# LC709203F_breakout.net
KiCad netlist of a schematic drawn in EAGLE
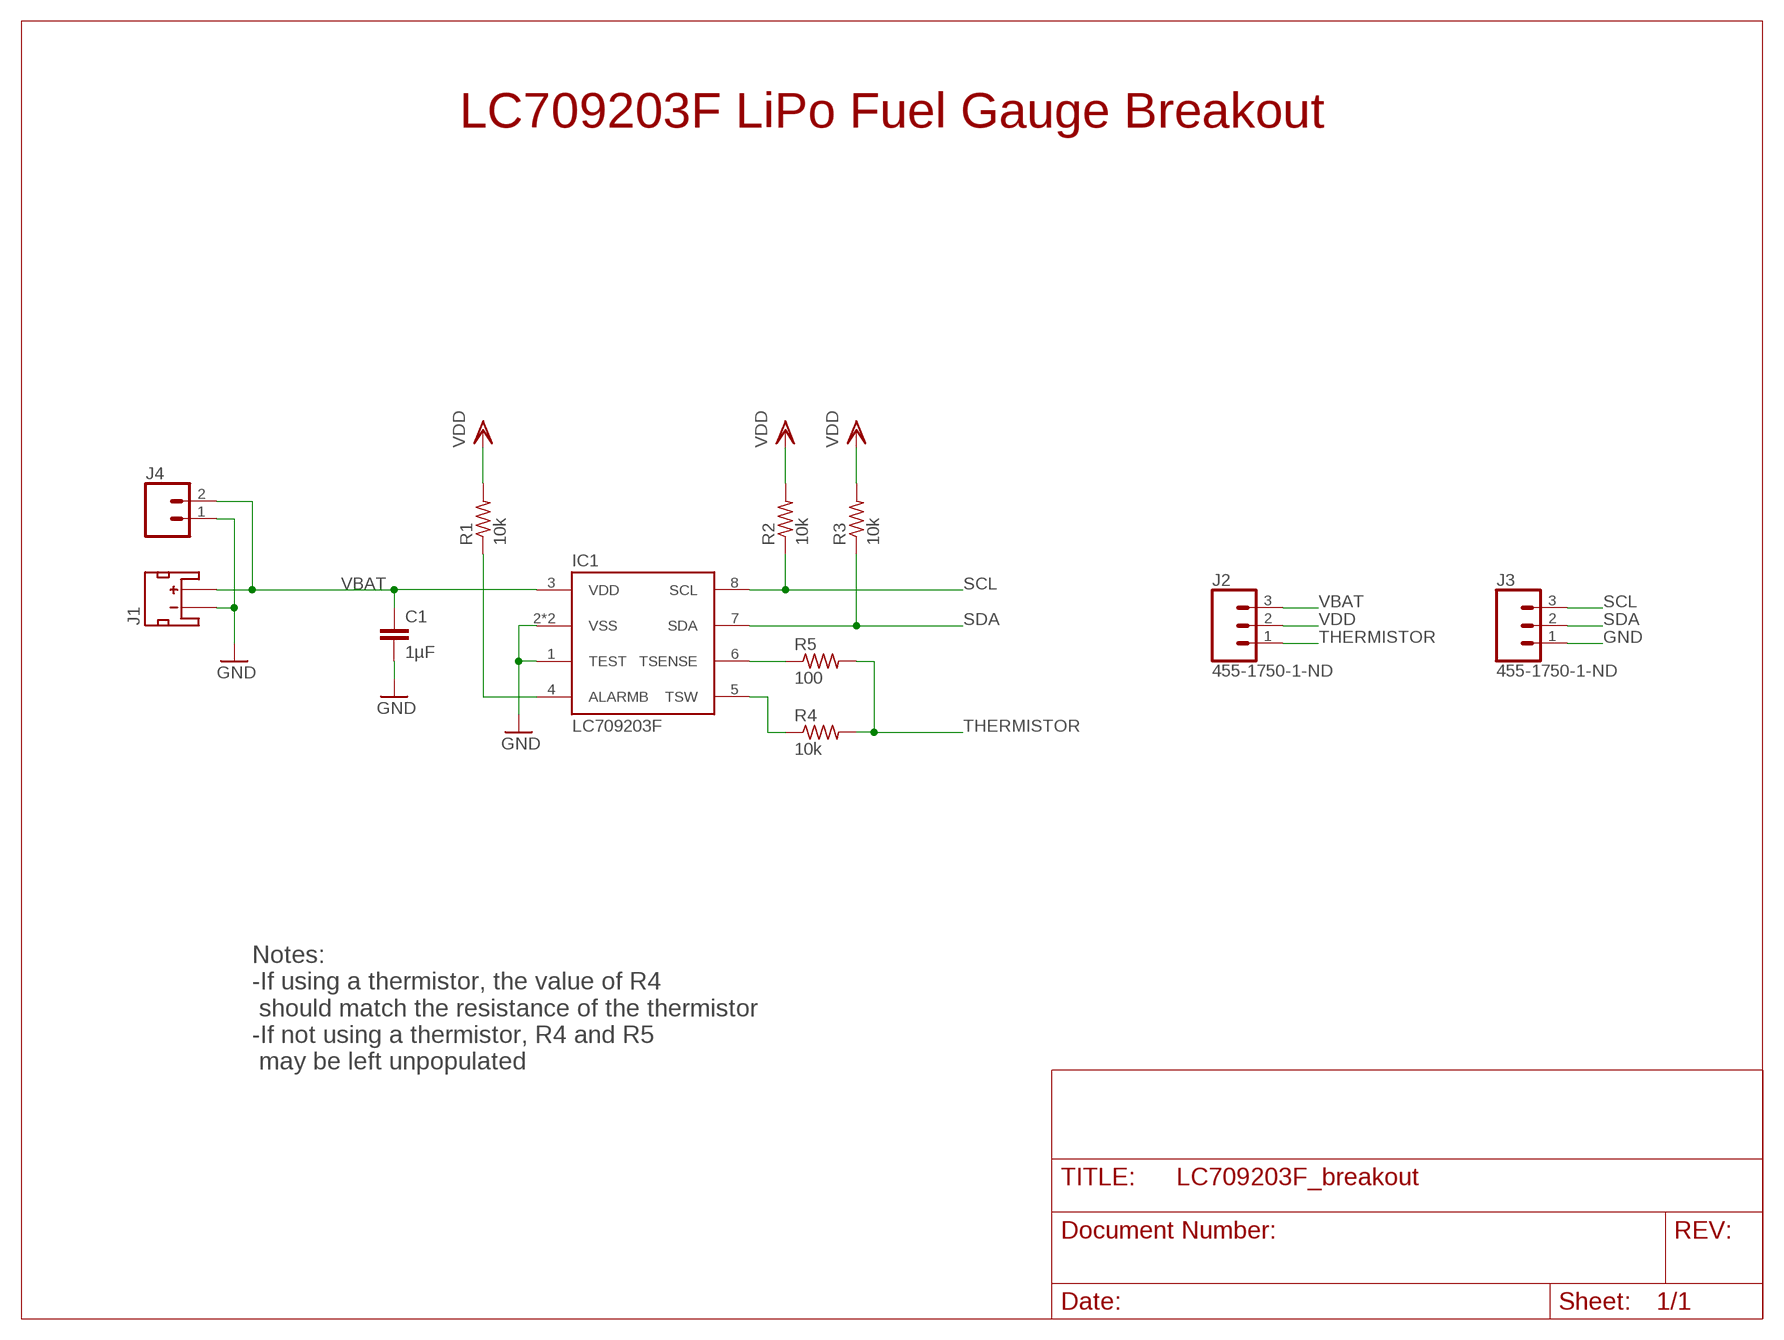
[diagram p0: schematic, sheet 1]

(export (version "E")
  (design (tool "Eeschema 10.0.6"))
  (components
    (comp (ref "C1")
      (value "1µF")
      (footprint "eagle-import:C0805")
      (fields
        (field (name "MANUFACTURER") "Murata Electronics North America")
        (field (name "PART#") "GRM21BR71A105KA01L")
        (field (name "TOLERANCE") "±10%")
      )
      (libsource (lib "eagle-import") (part "CAP_0805_MURATA_GRM_1UF"))
    )
    (comp (ref "IC1")
      (value "LC709203F")
      (footprint "eagle-import:WDFN8_ONSEMI")
      (fields (field (name "MANUFACTURER") "ON Semiconductor") (field (name "PART#") "LC709203FQH-01TWG"))
      (libsource (lib "eagle-import") (part "LC709203F"))
    )
    (comp (ref "J1")
      (value "S2B-PH-SM4-TB")
      (footprint "eagle-import:JST-2-SMD")
      (fields
        (field (name "MANUFACTURER") "JST Sales America Inc.")
        (field (name "PART#") "S2B-PH-SM4-TB(LF)(SN)")
      )
      (libsource (lib "eagle-import") (part "JST_2MM_MALE"))
    )
    (comp (ref "J2")
      (value "455-1750-1-ND")
      (footprint "eagle-import:1X03")
      (libsource (lib "eagle-import") (part "CONN_03"))
    )
    (comp (ref "J3")
      (value "455-1750-1-ND")
      (footprint "eagle-import:1X03")
      (libsource (lib "eagle-import") (part "CONN_03"))
    )
    (comp (ref "J4")
      (value "CONN_02")
      (footprint "eagle-import:1X02")
      (libsource (lib "eagle-import") (part "CONN_02"))
    )
    (comp (ref "R1")
      (value "10k")
      (footprint "eagle-import:R0805")
      (fields
        (field (name "MANUFACTURER") "Yageo")
        (field (name "PART#") "RC0805FR-0710KL")
        (field (name "POWER") "1/8W")
      )
      (libsource (lib "eagle-import") (part "RESISTOR_0805_YAGEO_RC_10K"))
    )
    (comp (ref "R2")
      (value "10k")
      (footprint "eagle-import:R0805")
      (fields
        (field (name "MANUFACTURER") "Yageo")
        (field (name "PART#") "RC0805FR-0710KL")
        (field (name "POWER") "1/8W")
      )
      (libsource (lib "eagle-import") (part "RESISTOR_0805_YAGEO_RC_10K"))
    )
    (comp (ref "R3")
      (value "10k")
      (footprint "eagle-import:R0805")
      (fields
        (field (name "MANUFACTURER") "Yageo")
        (field (name "PART#") "RC0805FR-0710KL")
        (field (name "POWER") "1/8W")
      )
      (libsource (lib "eagle-import") (part "RESISTOR_0805_YAGEO_RC_10K"))
    )
    (comp (ref "R4")
      (value "10k")
      (footprint "eagle-import:R0805")
      (fields
        (field (name "MANUFACTURER") "Yageo")
        (field (name "PART#") "RC0805FR-0710KL")
        (field (name "POWER") "1/8W")
      )
      (libsource (lib "eagle-import") (part "RESISTOR_0805_YAGEO_RC_10K"))
    )
    (comp (ref "R5")
      (value "100")
      (footprint "eagle-import:R0805")
      (fields
        (field (name "MANUFACTURER") "Yageo")
        (field (name "PART#") "RC0805FR-07100RL")
        (field (name "POWER") "1/8W")
      )
      (libsource (lib "eagle-import") (part "RESISTOR_0805_YAGEO_RC_100"))
    )
  )
  (nets
    (net (code "1") (name "/SCL") (class "Default")
      (node (ref "IC1") (pin "8") (pinfunction "SCL_8") (pintype "bidirectional"))
      (node (ref "J3") (pin "3") (pinfunction "3_3") (pintype "passive"))
      (node (ref "R2") (pin "1") (pinfunction "1_1") (pintype "passive"))
    )
    (net (code "2") (name "/SDA") (class "Default")
      (node (ref "IC1") (pin "7") (pinfunction "SDA_7") (pintype "bidirectional"))
      (node (ref "J3") (pin "2") (pinfunction "2_2") (pintype "passive"))
      (node (ref "R3") (pin "1") (pinfunction "1_1") (pintype "passive"))
    )
    (net (code "3") (name "/THERMISTOR") (class "Default")
      (node (ref "J2") (pin "1") (pinfunction "1_1") (pintype "passive"))
      (node (ref "R4") (pin "2") (pinfunction "2_2") (pintype "passive"))
      (node (ref "R5") (pin "2") (pinfunction "2_2") (pintype "passive"))
    )
    (net (code "4") (name "/VBAT") (class "Default")
      (node (ref "C1") (pin "1") (pinfunction "1_1") (pintype "passive"))
      (node (ref "IC1") (pin "3") (pinfunction "VDD_3") (pintype "bidirectional"))
      (node (ref "J1") (pin "2") (pinfunction "+_2") (pintype "bidirectional"))
      (node (ref "J2") (pin "3") (pinfunction "3_3") (pintype "passive"))
      (node (ref "J4") (pin "2") (pinfunction "2_2") (pintype "passive"))
    )
    (net (code "5") (name "GND") (class "Default")
      (node (ref "C1") (pin "2") (pinfunction "2_2") (pintype "passive"))
      (node (ref "IC1") (pin "1") (pinfunction "TEST_1") (pintype "bidirectional"))
      (node (ref "IC1") (pin "2") (pinfunction "VSS_2") (pintype "bidirectional"))
      (node (ref "IC1") (pin "9") (pinfunction "VSS_9") (pintype "bidirectional"))
      (node (ref "J1") (pin "1") (pinfunction "-_1") (pintype "bidirectional"))
      (node (ref "J3") (pin "1") (pinfunction "1_1") (pintype "passive"))
      (node (ref "J4") (pin "1") (pinfunction "1_1") (pintype "passive"))
    )
    (net (code "6") (name "Net-(IC1-ALARMB)") (class "Default")
      (node (ref "IC1") (pin "4") (pinfunction "ALARMB_4") (pintype "bidirectional"))
      (node (ref "R1") (pin "1") (pinfunction "1_1") (pintype "passive"))
    )
    (net (code "7") (name "Net-(IC1-TSENSE)") (class "Default")
      (node (ref "IC1") (pin "6") (pinfunction "TSENSE_6") (pintype "bidirectional"))
      (node (ref "R5") (pin "1") (pinfunction "1_1") (pintype "passive"))
    )
    (net (code "8") (name "Net-(IC1-TSW)") (class "Default")
      (node (ref "IC1") (pin "5") (pinfunction "TSW_5") (pintype "bidirectional"))
      (node (ref "R4") (pin "1") (pinfunction "1_1") (pintype "passive"))
    )
    (net (code "9") (name "VDD") (class "Default")
      (node (ref "J2") (pin "2") (pinfunction "2_2") (pintype "passive"))
      (node (ref "R1") (pin "2") (pinfunction "2_2") (pintype "passive"))
      (node (ref "R2") (pin "2") (pinfunction "2_2") (pintype "passive"))
      (node (ref "R3") (pin "2") (pinfunction "2_2") (pintype "passive"))
    )
    (net (code "10") (name "unconnected-(J1-PAD1-PadNC1)") (class "Default")
      (node (ref "J1") (pin "NC1") (pinfunction "PAD1_NC1") (pintype "bidirectional"))
    )
    (net (code "11") (name "unconnected-(J1-PAD2-PadNC2)") (class "Default")
      (node (ref "J1") (pin "NC2") (pinfunction "PAD2_NC2") (pintype "bidirectional"))
    )
  )
)
